# fancyblink.net
KiCad netlist of a schematic drawn in EAGLE
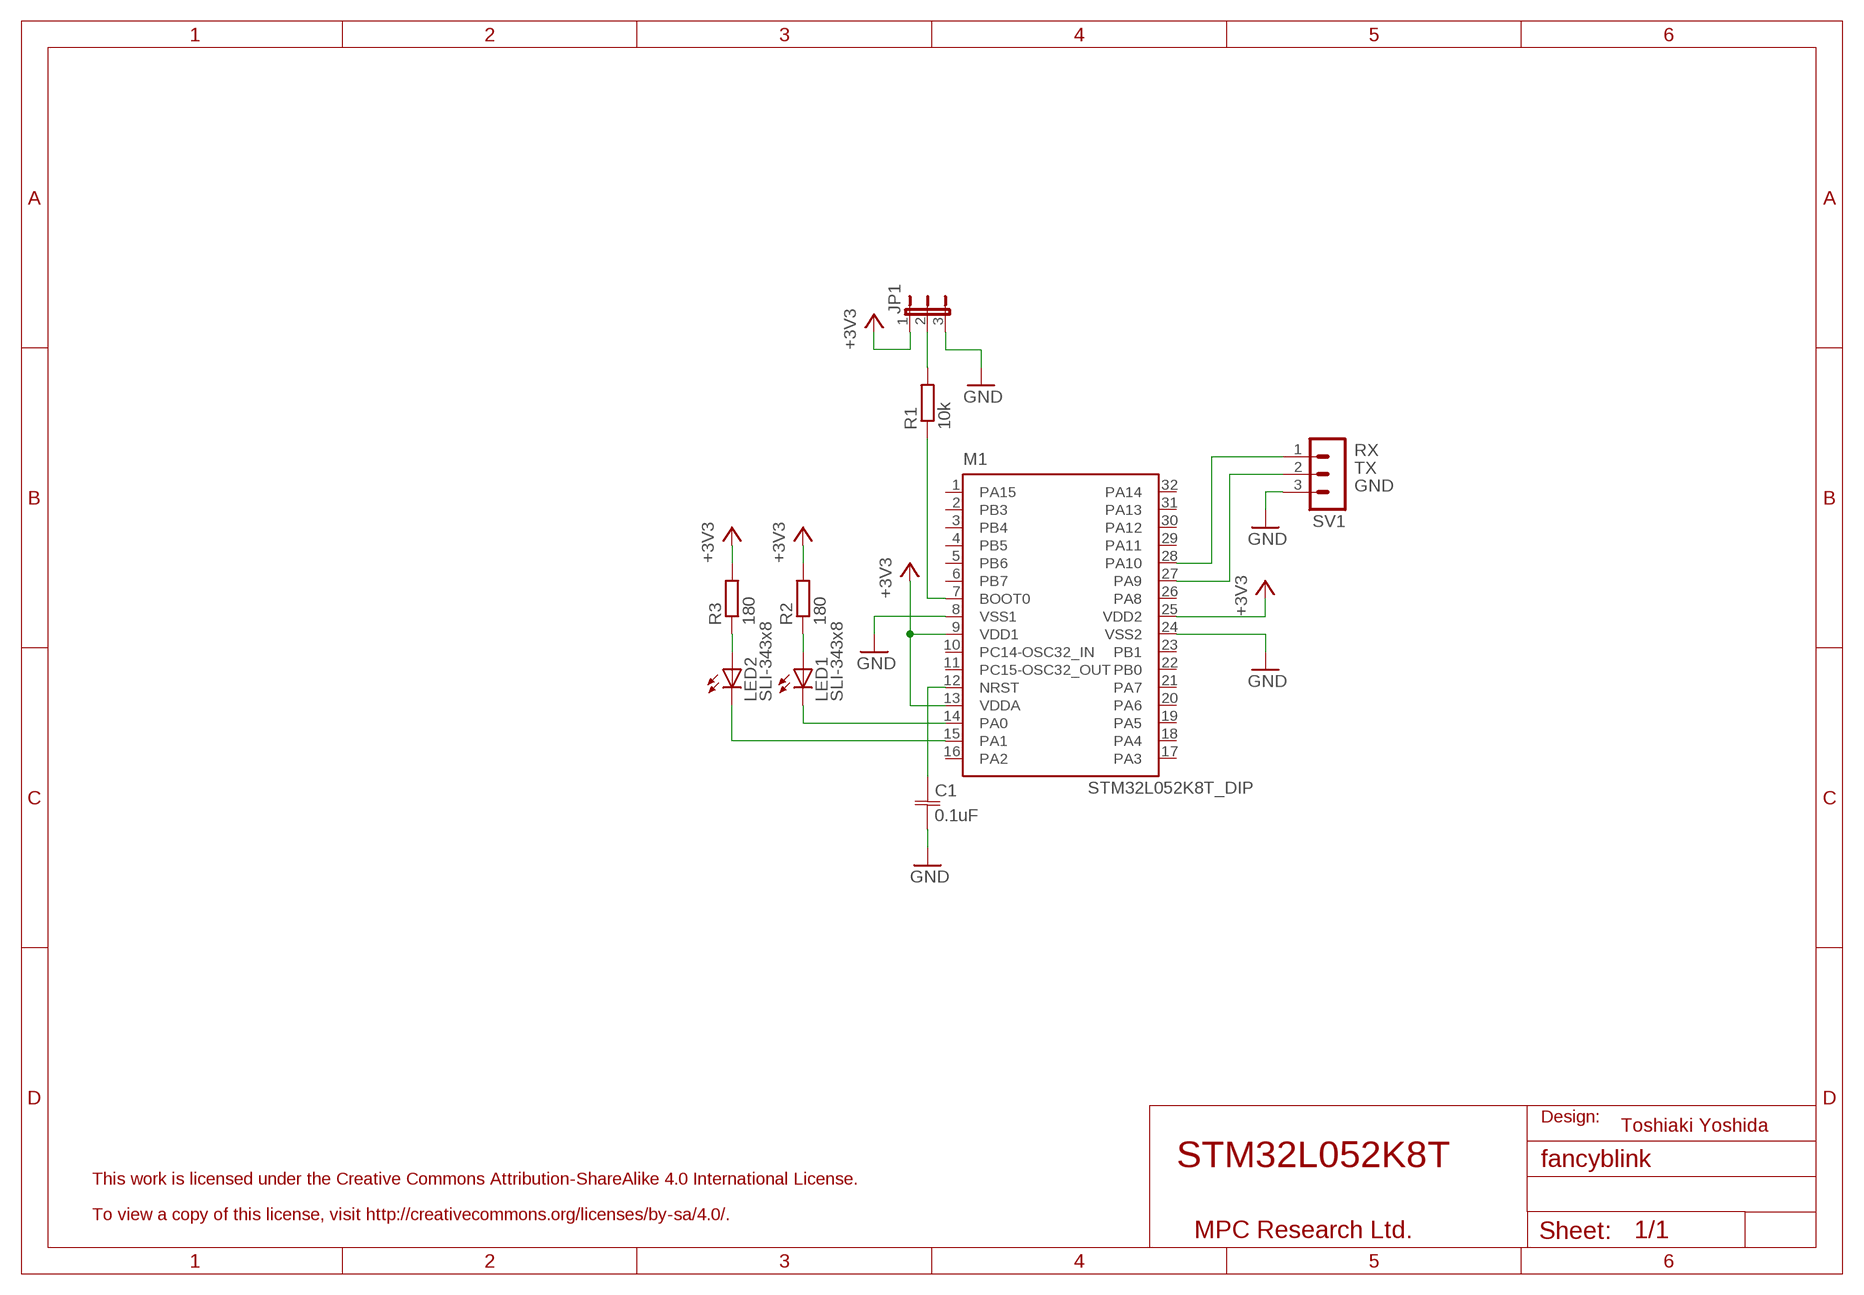
[diagram p0: schematic, sheet 1]

(export (version "E")
  (design (tool "Eeschema 10.0.6"))
  (components
    (comp (ref "C1")
      (value "0.1uF")
      (footprint "eagle-import:C050-024X044")
      (libsource (lib "eagle-import") (part "C-JIS050-024X044"))
    )
    (comp (ref "JP1")
      (value "JP2E")
      (footprint "eagle-import:JP2")
      (libsource (lib "eagle-import") (part "JP2E"))
    )
    (comp (ref "LED1")
      (value "SLI-343x8")
      (footprint "eagle-import:LED3MM")
      (libsource (lib "eagle-import") (part "LED3MM"))
    )
    (comp (ref "LED2")
      (value "SLI-343x8")
      (footprint "eagle-import:LED3MM")
      (libsource (lib "eagle-import") (part "LED3MM"))
    )
    (comp (ref "M1")
      (value "STM32L052K8T_DIP")
      (footprint "eagle-import:DIP32")
      (libsource (lib "eagle-import") (part "STM32L052K8T_DIP"))
    )
    (comp (ref "R1")
      (value "10k")
      (footprint "eagle-import:0207_2V")
      (libsource (lib "eagle-import") (part "R-EU_0207/2V"))
    )
    (comp (ref "R2")
      (value "180")
      (footprint "eagle-import:0207_2V")
      (libsource (lib "eagle-import") (part "R-EU_0207/2V"))
    )
    (comp (ref "R3")
      (value "180")
      (footprint "eagle-import:0207_2V")
      (libsource (lib "eagle-import") (part "R-EU_0207/2V"))
    )
    (comp (ref "SV1")
      (value "MA03-1")
      (footprint "eagle-import:MA03-1")
      (libsource (lib "eagle-import") (part "MA03-1"))
    )
  )
  (nets
    (net (code "1") (name "+3V3") (class "Default")
      (node (ref "JP1") (pin "1") (pinfunction "1_1") (pintype "passive"))
      (node (ref "M1") (pin "13") (pinfunction "VDDA_13") (pintype "power_in"))
      (node (ref "M1") (pin "25") (pinfunction "VDD2_25") (pintype "bidirectional"))
      (node (ref "M1") (pin "9") (pinfunction "VDD1_9") (pintype "power_in"))
      (node (ref "R2") (pin "2") (pinfunction "2_2") (pintype "passive"))
      (node (ref "R3") (pin "2") (pinfunction "2_2") (pintype "passive"))
    )
    (net (code "2") (name "GND") (class "Default")
      (node (ref "C1") (pin "2") (pinfunction "2_2") (pintype "passive"))
      (node (ref "JP1") (pin "3") (pinfunction "3_3") (pintype "passive"))
      (node (ref "M1") (pin "24") (pinfunction "VSS2_24") (pintype "power_in"))
      (node (ref "M1") (pin "8") (pinfunction "VSS1_8") (pintype "power_in"))
      (node (ref "SV1") (pin "3") (pinfunction "3_3") (pintype "passive"))
    )
    (net (code "3") (name "Net-(JP1-Pad2)") (class "Default")
      (node (ref "JP1") (pin "2") (pinfunction "2_2") (pintype "passive"))
      (node (ref "R1") (pin "2") (pinfunction "2_2") (pintype "passive"))
    )
    (net (code "4") (name "Net-(LED1-C)") (class "Default")
      (node (ref "LED1") (pin "K") (pinfunction "C_K") (pintype "passive"))
      (node (ref "M1") (pin "14") (pinfunction "PA0_14") (pintype "bidirectional"))
    )
    (net (code "5") (name "Net-(LED1-PadA)") (class "Default")
      (node (ref "LED1") (pin "A") (pinfunction "A_A") (pintype "passive"))
      (node (ref "R2") (pin "1") (pinfunction "1_1") (pintype "passive"))
    )
    (net (code "6") (name "Net-(LED2-C)") (class "Default")
      (node (ref "LED2") (pin "K") (pinfunction "C_K") (pintype "passive"))
      (node (ref "M1") (pin "15") (pinfunction "PA1_15") (pintype "bidirectional"))
    )
    (net (code "7") (name "Net-(LED2-PadA)") (class "Default")
      (node (ref "LED2") (pin "A") (pinfunction "A_A") (pintype "passive"))
      (node (ref "R3") (pin "1") (pinfunction "1_1") (pintype "passive"))
    )
    (net (code "8") (name "Net-(M1-BOOT0)") (class "Default")
      (node (ref "M1") (pin "7") (pinfunction "BOOT0_7") (pintype "bidirectional"))
      (node (ref "R1") (pin "1") (pinfunction "1_1") (pintype "passive"))
    )
    (net (code "9") (name "Net-(M1-NRST)") (class "Default")
      (node (ref "C1") (pin "1") (pinfunction "1_1") (pintype "passive"))
      (node (ref "M1") (pin "12") (pinfunction "NRST_12") (pintype "bidirectional"))
    )
    (net (code "10") (name "Net-(M1-PA9)") (class "Default")
      (node (ref "M1") (pin "27") (pinfunction "PA9_27") (pintype "bidirectional"))
      (node (ref "SV1") (pin "2") (pinfunction "2_2") (pintype "passive"))
    )
    (net (code "11") (name "Net-(M1-PA10)") (class "Default")
      (node (ref "M1") (pin "28") (pinfunction "PA10_28") (pintype "bidirectional"))
      (node (ref "SV1") (pin "1") (pinfunction "1_1") (pintype "passive"))
    )
    (net (code "12") (name "unconnected-(M1-PA2-Pad16)") (class "Default")
      (node (ref "M1") (pin "16") (pinfunction "PA2_16") (pintype "bidirectional"))
    )
    (net (code "13") (name "unconnected-(M1-PA3-Pad17)") (class "Default")
      (node (ref "M1") (pin "17") (pinfunction "PA3_17") (pintype "bidirectional"))
    )
    (net (code "14") (name "unconnected-(M1-PA4-Pad18)") (class "Default")
      (node (ref "M1") (pin "18") (pinfunction "PA4_18") (pintype "bidirectional"))
    )
    (net (code "15") (name "unconnected-(M1-PA5-Pad19)") (class "Default")
      (node (ref "M1") (pin "19") (pinfunction "PA5_19") (pintype "bidirectional"))
    )
    (net (code "16") (name "unconnected-(M1-PA6-Pad20)") (class "Default")
      (node (ref "M1") (pin "20") (pinfunction "PA6_20") (pintype "bidirectional"))
    )
    (net (code "17") (name "unconnected-(M1-PA7-Pad21)") (class "Default")
      (node (ref "M1") (pin "21") (pinfunction "PA7_21") (pintype "bidirectional"))
    )
    (net (code "18") (name "unconnected-(M1-PA8-Pad26)") (class "Default")
      (node (ref "M1") (pin "26") (pinfunction "PA8_26") (pintype "bidirectional"))
    )
    (net (code "19") (name "unconnected-(M1-PA11-Pad29)") (class "Default")
      (node (ref "M1") (pin "29") (pinfunction "PA11_29") (pintype "bidirectional"))
    )
    (net (code "20") (name "unconnected-(M1-PA12-Pad30)") (class "Default")
      (node (ref "M1") (pin "30") (pinfunction "PA12_30") (pintype "bidirectional"))
    )
    (net (code "21") (name "unconnected-(M1-PA13-Pad31)") (class "Default")
      (node (ref "M1") (pin "31") (pinfunction "PA13_31") (pintype "bidirectional"))
    )
    (net (code "22") (name "unconnected-(M1-PA14-Pad32)") (class "Default")
      (node (ref "M1") (pin "32") (pinfunction "PA14_32") (pintype "bidirectional"))
    )
    (net (code "23") (name "unconnected-(M1-PA15-Pad1)") (class "Default")
      (node (ref "M1") (pin "1") (pinfunction "PA15_1") (pintype "bidirectional"))
    )
    (net (code "24") (name "unconnected-(M1-PB0-Pad22)") (class "Default")
      (node (ref "M1") (pin "22") (pinfunction "PB0_22") (pintype "bidirectional"))
    )
    (net (code "25") (name "unconnected-(M1-PB1-Pad23)") (class "Default")
      (node (ref "M1") (pin "23") (pinfunction "PB1_23") (pintype "bidirectional"))
    )
    (net (code "26") (name "unconnected-(M1-PB3-Pad2)") (class "Default")
      (node (ref "M1") (pin "2") (pinfunction "PB3_2") (pintype "bidirectional"))
    )
    (net (code "27") (name "unconnected-(M1-PB4-Pad3)") (class "Default")
      (node (ref "M1") (pin "3") (pinfunction "PB4_3") (pintype "bidirectional"))
    )
    (net (code "28") (name "unconnected-(M1-PB5-Pad4)") (class "Default")
      (node (ref "M1") (pin "4") (pinfunction "PB5_4") (pintype "bidirectional"))
    )
    (net (code "29") (name "unconnected-(M1-PB6-Pad5)") (class "Default")
      (node (ref "M1") (pin "5") (pinfunction "PB6_5") (pintype "bidirectional"))
    )
    (net (code "30") (name "unconnected-(M1-PB7-Pad6)") (class "Default")
      (node (ref "M1") (pin "6") (pinfunction "PB7_6") (pintype "bidirectional"))
    )
    (net (code "31") (name "unconnected-(M1-PC14-OSC32_IN-Pad10)") (class "Default")
      (node (ref "M1") (pin "10") (pinfunction "PC14-OSC32_IN_10") (pintype "bidirectional"))
    )
    (net (code "32") (name "unconnected-(M1-PC15-OSC32_OUT-Pad11)") (class "Default")
      (node (ref "M1") (pin "11") (pinfunction "PC15-OSC32_OUT_11") (pintype "bidirectional"))
    )
  )
)
